# LED_Module.net
KiCad netlist of a schematic drawn in Altium Designer
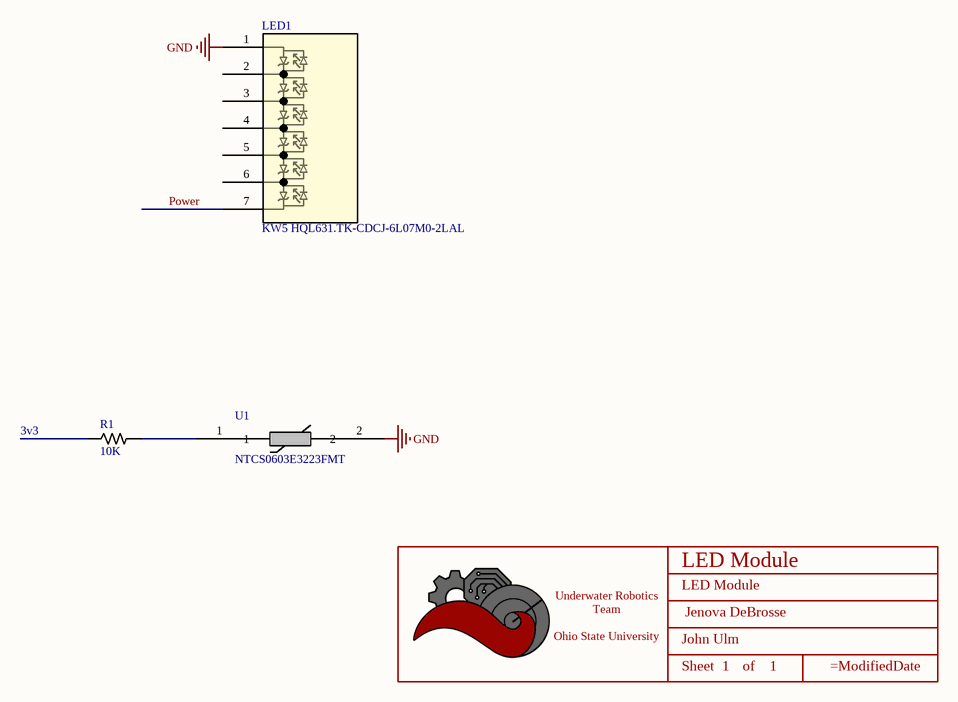
[diagram p0: LED_Module.SchDoc]

(export (version "E")
  (design (tool "Eeschema 10.0.6"))
  (components
    (comp (ref "*")
      (value "Title_Block")
      (footprint "LOGO")
      (description "UWRT Schematic Title Block Template\r\n\r\nCreated June 2021, Dylan Trainor")
      (libsource (lib "UWRT") (part "Title_Block"))
    )
    (comp (ref "LED1")
      (value "KW5 HQL631.TK-CDCJ-6L07M0-2LAL")
      (footprint "KW5HQL_OSR")
      (description "No Description Available")
      (libsource (lib "Diodes") (part "KW5 HQL631.TK-CDCJ-6L07M0-2LAL"))
    )
    (comp (ref "R1")
      (value "10k Ohm 0.5% 1/10W")
      (footprint "RESISTOR_0603")
      (description "RES 10k OHM 0.5% 1/10W 0603")
      (fields
        (field (name "TOLERANCE") "+/- 0.5%")
        (field (name "VALUE  (OHMS)") "10K")
        (field (name "MADE BY") "Robert Pafford")
      )
      (libsource (lib "Resistors") (part "RESISTOR_10K_0.5%_0603"))
    )
    (comp (ref "U1")
      (value "NTCS0603E3223FMT")
      (footprint "NTCS0603_VIS")
      (fields (field (name "TOLERANCE") "1%"))
      (libsource (lib "Altium Content Vault") (part "NTCS0603E3223FMT"))
    )
  )
  (nets
    (net (code "1") (name "/Power") (class "Default")
      (node (ref "LED1") (pin "7") (pinfunction "7_7") (pintype "passive"))
    )
    (net (code "2") (name "GND") (class "Default")
      (node (ref "LED1") (pin "1") (pinfunction "1_1") (pintype "passive"))
      (node (ref "U1") (pin "2") (pinfunction "2_2") (pintype "passive"))
    )
    (net (code "3") (name "Net-(R1-Pad1)") (class "Default")
      (node (ref "R1") (pin "1") (pinfunction "1_1") (pintype "passive"))
      (node (ref "U1") (pin "1") (pinfunction "1_1") (pintype "passive"))
    )
    (net (code "4") (name "unconnected-(LED1-Pad2)") (class "Default")
      (node (ref "LED1") (pin "2") (pinfunction "2_2") (pintype "passive"))
    )
    (net (code "5") (name "unconnected-(LED1-Pad3)") (class "Default")
      (node (ref "LED1") (pin "3") (pinfunction "3_3") (pintype "passive"))
    )
    (net (code "6") (name "unconnected-(LED1-Pad4)") (class "Default")
      (node (ref "LED1") (pin "4") (pinfunction "4_4") (pintype "passive"))
    )
    (net (code "7") (name "unconnected-(LED1-Pad5)") (class "Default")
      (node (ref "LED1") (pin "5") (pinfunction "5_5") (pintype "passive"))
    )
    (net (code "8") (name "unconnected-(LED1-Pad6)") (class "Default")
      (node (ref "LED1") (pin "6") (pinfunction "6_6") (pintype "passive"))
    )
    (net (code "9") (name "unconnected-(R1-Pad2)") (class "Default")
      (node (ref "R1") (pin "2") (pinfunction "2_2") (pintype "passive"))
    )
  )
)
